# tsc.net
KiCad netlist of a schematic drawn in EAGLE
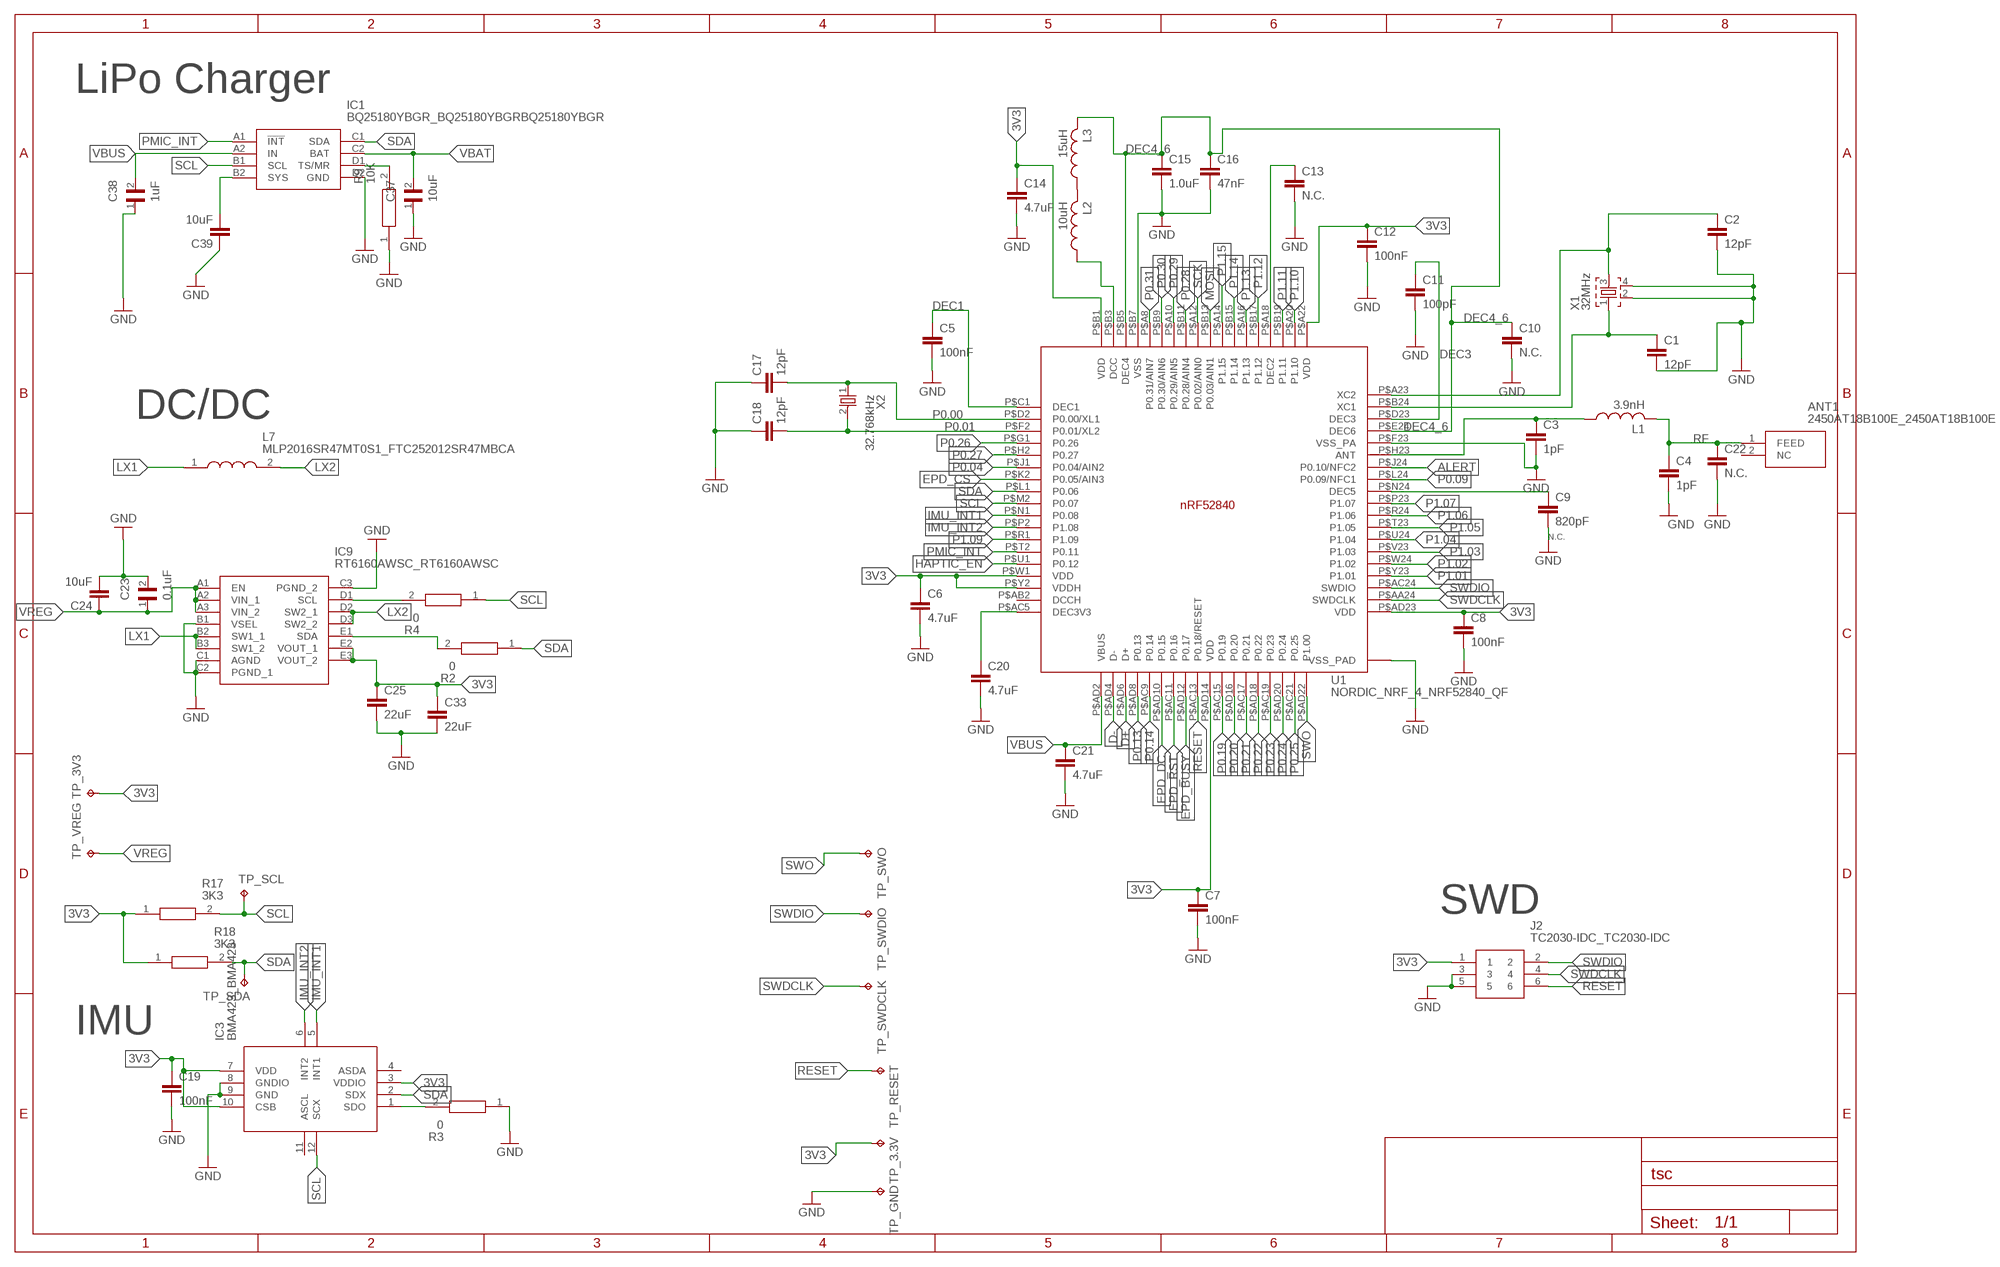
[diagram p0: schematic, sheet 1, part 1 of 2]
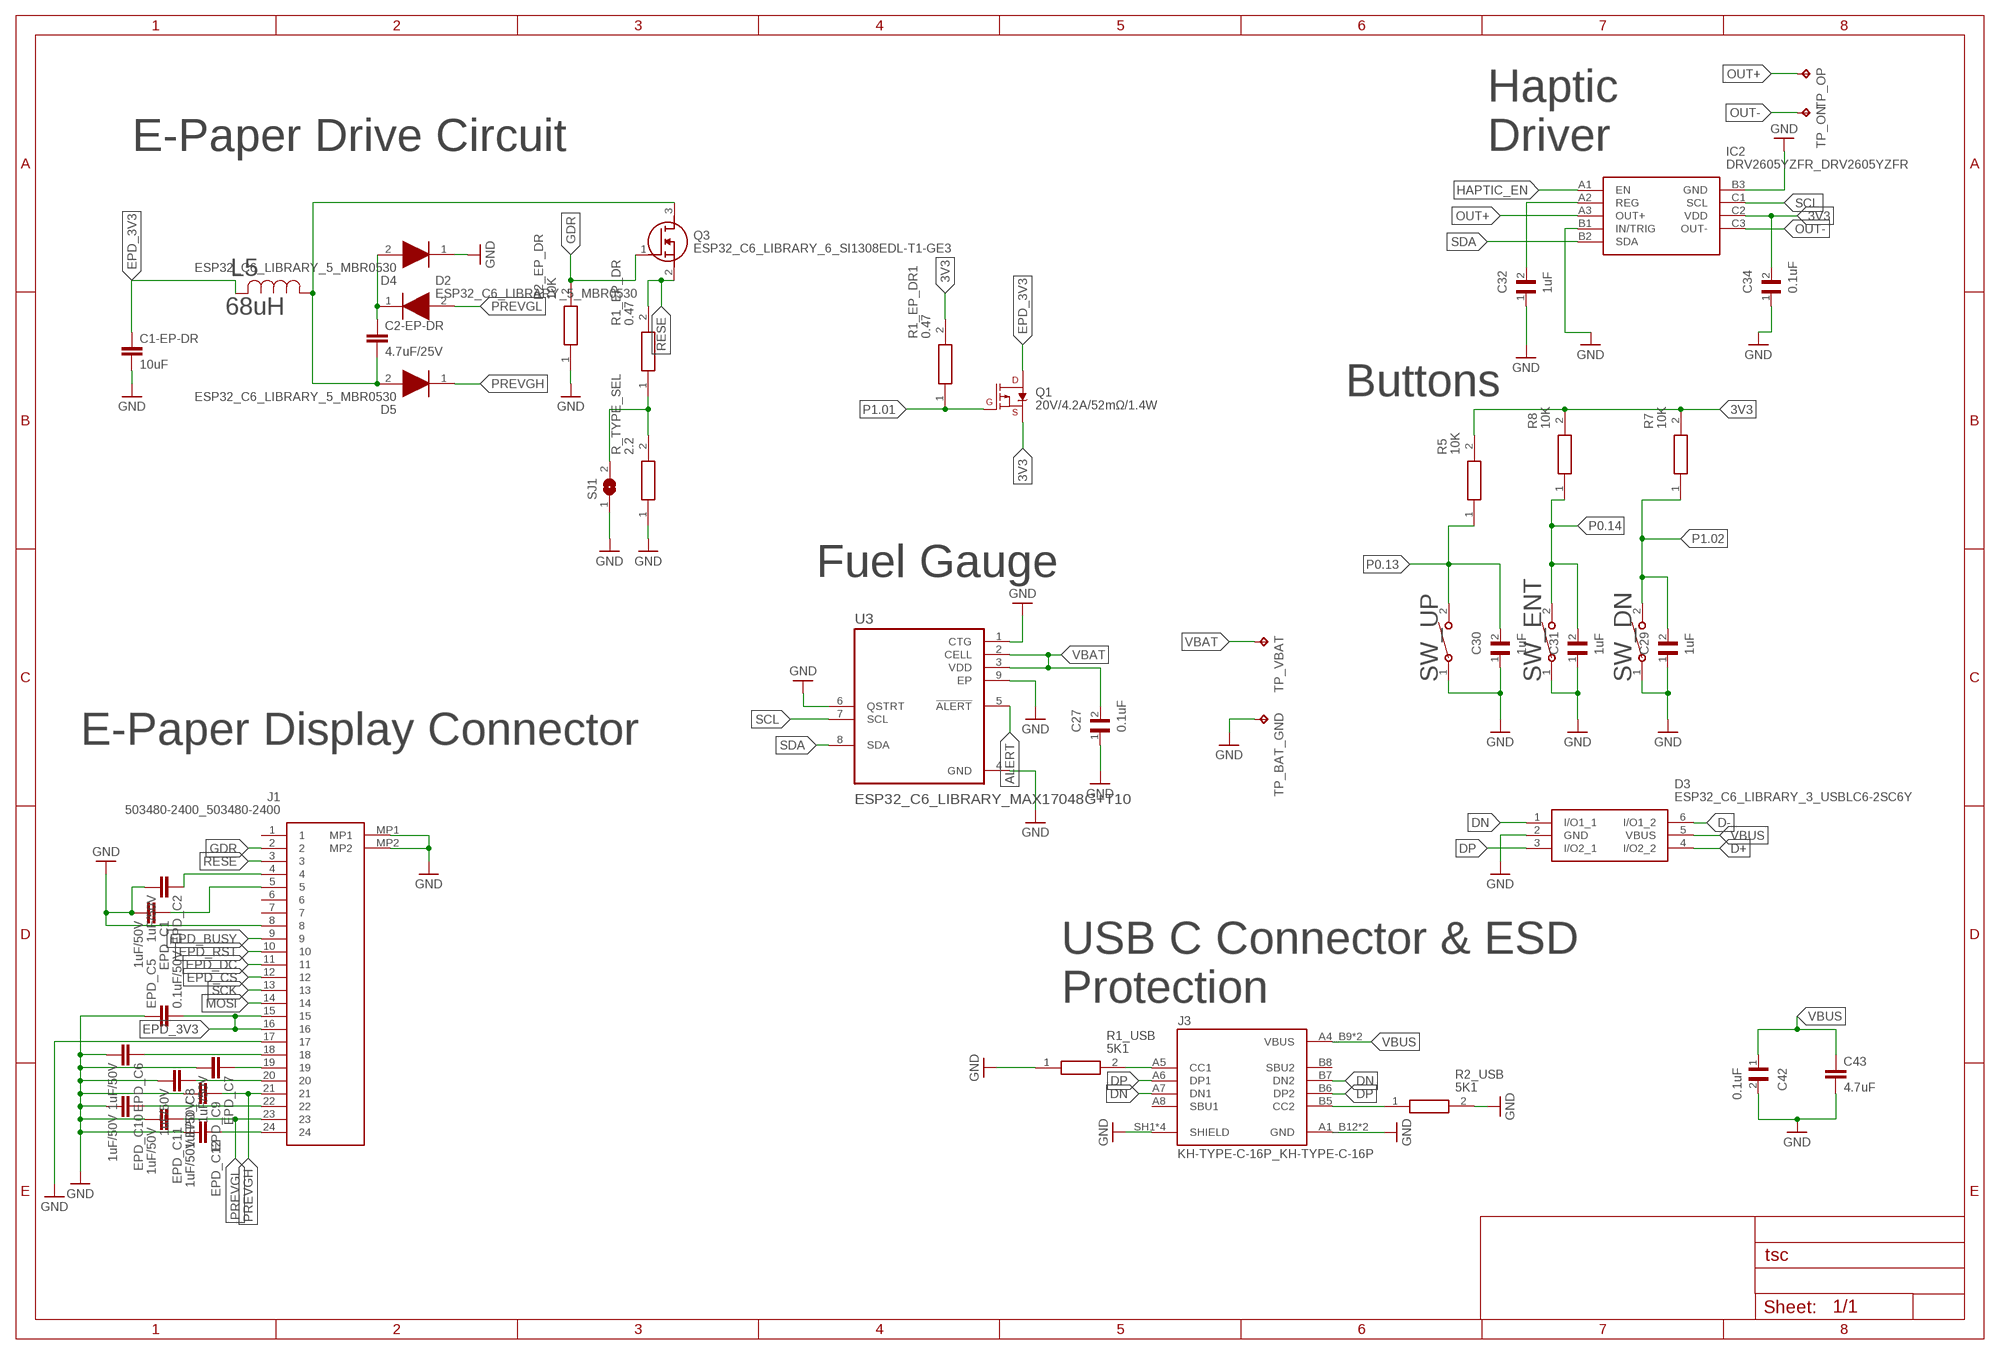
[diagram p1: schematic, sheet 1, part 2 of 2]

(export (version "E")
  (design (tool "Eeschema 10.0.6"))
  (components
    (comp (ref "ANT1")
      (value "2450AT18B100E_2450AT18B100E")
      (footprint "eagle-import:2450AT18B100E_ANTC3216X140N")
      (fields
        (field (name "ARROW_PART_NUMBER") "2450AT18B100E")
        (field (name "MOUSER_PART_NUMBER") "609-2450AT18B100E")
      )
      (libsource (lib "eagle-import") (part "2450AT18B100E_2450AT18B100E"))
    )
    (comp (ref "C1")
      (value "12pF")
      (footprint "eagle-import:NORDIC_NRF_3_RESC0201_L")
      (libsource (lib "eagle-import") (part "NORDIC_NRF_3_CAPACITOR_0201_L"))
    )
    (comp (ref "C1-EP-DR")
      (value "10uF")
      (footprint "eagle-import:NORDIC_NRF_3_RESC0201_L")
      (libsource (lib "eagle-import") (part "NORDIC_NRF_3_CAPACITOR_0201_L"))
    )
    (comp (ref "C2")
      (value "12pF")
      (footprint "eagle-import:NORDIC_NRF_3_RESC0201_L")
      (libsource (lib "eagle-import") (part "NORDIC_NRF_3_CAPACITOR_0201_L"))
    )
    (comp (ref "C2-EP-DR")
      (value "4.7uF/25V")
      (footprint "eagle-import:NORDIC_NRF_3_RESC0201_L")
      (libsource (lib "eagle-import") (part "NORDIC_NRF_3_CAPACITOR_0201_L"))
    )
    (comp (ref "C3")
      (value "1pF")
      (footprint "eagle-import:NORDIC_NRF_3_RESC0201_L")
      (libsource (lib "eagle-import") (part "NORDIC_NRF_3_CAPACITOR_0201_L"))
    )
    (comp (ref "C4")
      (value "1pF")
      (footprint "eagle-import:NORDIC_NRF_3_RESC0201_L")
      (libsource (lib "eagle-import") (part "NORDIC_NRF_3_CAPACITOR_0201_L"))
    )
    (comp (ref "C5")
      (value "100nF")
      (footprint "eagle-import:NORDIC_NRF_3_RESC0201_L")
      (libsource (lib "eagle-import") (part "NORDIC_NRF_3_CAPACITOR_0201_L"))
    )
    (comp (ref "C6")
      (value "4.7uF")
      (footprint "eagle-import:PERFECT_0402_0402")
      (libsource (lib "eagle-import") (part "PERFECT_0402_CAP_0402"))
    )
    (comp (ref "C7")
      (value "100nF")
      (footprint "eagle-import:NORDIC_NRF_3_RESC0201_L")
      (libsource (lib "eagle-import") (part "NORDIC_NRF_3_CAPACITOR_0201_L"))
    )
    (comp (ref "C8")
      (value "100nF")
      (footprint "eagle-import:NORDIC_NRF_3_RESC0201_L")
      (libsource (lib "eagle-import") (part "NORDIC_NRF_3_CAPACITOR_0201_L"))
    )
    (comp (ref "C9")
      (value "820pF")
      (footprint "eagle-import:NORDIC_NRF_3_RESC0201_L")
      (libsource (lib "eagle-import") (part "NORDIC_NRF_3_CAPACITOR_0201_L"))
    )
    (comp (ref "C10")
      (value "N.C.")
      (footprint "eagle-import:NORDIC_NRF_3_RESC0201_L")
      (libsource (lib "eagle-import") (part "NORDIC_NRF_3_CAPACITOR_0201_L"))
    )
    (comp (ref "C11")
      (value "100pF")
      (footprint "eagle-import:NORDIC_NRF_3_RESC0201_L")
      (libsource (lib "eagle-import") (part "NORDIC_NRF_3_CAPACITOR_0201_L"))
    )
    (comp (ref "C12")
      (value "100nF")
      (footprint "eagle-import:NORDIC_NRF_3_RESC0201_L")
      (libsource (lib "eagle-import") (part "NORDIC_NRF_3_CAPACITOR_0201_L"))
    )
    (comp (ref "C13")
      (value "N.C.")
      (footprint "eagle-import:NORDIC_NRF_3_RESC0201_L")
      (libsource (lib "eagle-import") (part "NORDIC_NRF_3_CAPACITOR_0201_L"))
    )
    (comp (ref "C14")
      (value "4.7uF")
      (footprint "eagle-import:PERFECT_0402_0402")
      (libsource (lib "eagle-import") (part "PERFECT_0402_CAP_0402"))
    )
    (comp (ref "C15")
      (value "1.0uF")
      (footprint "eagle-import:PERFECT_0402_0402")
      (libsource (lib "eagle-import") (part "PERFECT_0402_CAP_0402"))
    )
    (comp (ref "C16")
      (value "47nF")
      (footprint "eagle-import:NORDIC_NRF_3_RESC0201_L")
      (libsource (lib "eagle-import") (part "NORDIC_NRF_3_CAPACITOR_0201_L"))
    )
    (comp (ref "C17")
      (value "12pF")
      (footprint "eagle-import:NORDIC_NRF_3_RESC0201_L")
      (libsource (lib "eagle-import") (part "NORDIC_NRF_3_CAPACITOR_0201_L"))
    )
    (comp (ref "C18")
      (value "12pF")
      (footprint "eagle-import:NORDIC_NRF_3_RESC0201_L")
      (libsource (lib "eagle-import") (part "NORDIC_NRF_3_CAPACITOR_0201_L"))
    )
    (comp (ref "C19")
      (value "100nF")
      (footprint "eagle-import:NORDIC_NRF_3_RESC0201_L")
      (libsource (lib "eagle-import") (part "NORDIC_NRF_3_CAPACITOR_0201_L"))
    )
    (comp (ref "C20")
      (value "4.7uF")
      (footprint "eagle-import:PERFECT_0402_0402")
      (libsource (lib "eagle-import") (part "PERFECT_0402_CAP_0402"))
    )
    (comp (ref "C21")
      (value "4.7uF")
      (footprint "eagle-import:PERFECT_0402_0402")
      (libsource (lib "eagle-import") (part "PERFECT_0402_CAP_0402"))
    )
    (comp (ref "C22")
      (value "N.C.")
      (footprint "eagle-import:NORDIC_NRF_3_RESC0201_L")
      (libsource (lib "eagle-import") (part "NORDIC_NRF_3_CAPACITOR_0201_L"))
    )
    (comp (ref "C23")
      (value "0.1uF")
      (footprint "eagle-import:GRM011R60J152KE01L_1_0201")
      (libsource (lib "eagle-import") (part "GRM011R60J152KE01L_1_GRM011R60J152KE01L"))
    )
    (comp (ref "C24")
      (value "10uF")
      (footprint "eagle-import:NORDIC_NRF_3_RESC0201_L")
      (libsource (lib "eagle-import") (part "NORDIC_NRF_3_CAPACITOR_0201_L"))
    )
    (comp (ref "C25")
      (value "22uF")
      (footprint "eagle-import:NORDIC_NRF_3_RESC0201_L")
      (libsource (lib "eagle-import") (part "NORDIC_NRF_3_CAPACITOR_0201_L"))
    )
    (comp (ref "C27")
      (value "0.1uF")
      (footprint "eagle-import:GRM011R60J152KE01L_1_0201")
      (libsource (lib "eagle-import") (part "GRM011R60J152KE01L_1_GRM011R60J152KE01L"))
    )
    (comp (ref "C29")
      (value "1uF")
      (footprint "eagle-import:GRM011R60J152KE01L_1_0201")
      (libsource (lib "eagle-import") (part "GRM011R60J152KE01L_1_GRM011R60J152KE01L"))
    )
    (comp (ref "C30")
      (value "1uF")
      (footprint "eagle-import:GRM011R60J152KE01L_1_0201")
      (libsource (lib "eagle-import") (part "GRM011R60J152KE01L_1_GRM011R60J152KE01L"))
    )
    (comp (ref "C31")
      (value "1uF")
      (footprint "eagle-import:GRM011R60J152KE01L_1_0201")
      (libsource (lib "eagle-import") (part "GRM011R60J152KE01L_1_GRM011R60J152KE01L"))
    )
    (comp (ref "C32")
      (value "1uF")
      (footprint "eagle-import:GRM011R60J152KE01L_1_0201")
      (libsource (lib "eagle-import") (part "GRM011R60J152KE01L_1_GRM011R60J152KE01L"))
    )
    (comp (ref "C33")
      (value "22uF")
      (footprint "eagle-import:NORDIC_NRF_3_RESC0201_L")
      (libsource (lib "eagle-import") (part "NORDIC_NRF_3_CAPACITOR_0201_L"))
    )
    (comp (ref "C34")
      (value "0.1uF")
      (footprint "eagle-import:GRM011R60J152KE01L_1_0201")
      (libsource (lib "eagle-import") (part "GRM011R60J152KE01L_1_GRM011R60J152KE01L"))
    )
    (comp (ref "C37")
      (value "10uF")
      (footprint "eagle-import:GRM011R60J152KE01L_1_0201")
      (libsource (lib "eagle-import") (part "GRM011R60J152KE01L_1_GRM011R60J152KE01L"))
    )
    (comp (ref "C38")
      (value "1uF")
      (footprint "eagle-import:GRM011R60J152KE01L_1_0201")
      (libsource (lib "eagle-import") (part "GRM011R60J152KE01L_1_GRM011R60J152KE01L"))
    )
    (comp (ref "C39")
      (value "10uF")
      (footprint "eagle-import:NORDIC_NRF_3_RESC0201_L")
      (libsource (lib "eagle-import") (part "NORDIC_NRF_3_CAPACITOR_0201_L"))
    )
    (comp (ref "C42")
      (value "0.1uF")
      (footprint "eagle-import:GRM011R60J152KE01L_1_0201")
      (libsource (lib "eagle-import") (part "GRM011R60J152KE01L_1_GRM011R60J152KE01L"))
    )
    (comp (ref "C43")
      (value "4.7uF")
      (footprint "eagle-import:NORDIC_NRF_3_RESC0201_L")
      (libsource (lib "eagle-import") (part "NORDIC_NRF_3_CAPACITOR_0201_L"))
    )
    (comp (ref "D2")
      (value "ESP32_C6_LIBRARY_5_MBR0530")
      (footprint "eagle-import:ESP32_C6_LIBRARY_5_SOD3716X135N")
      (fields (field (name "MF") "ON Semiconductor") (field (name "MP") "MBR0530"))
      (libsource (lib "eagle-import") (part "ESP32_C6_LIBRARY_5_MBR0530"))
    )
    (comp (ref "D3")
      (value "ESP32_C6_LIBRARY_3_USBLC6-2SC6Y")
      (footprint "eagle-import:ESP32_C6_LIBRARY_3_SOT95P280X145-6N")
      (fields (field (name "MF") "STMicroelectronics") (field (name "MP") "USBLC6-2SC6Y"))
      (libsource (lib "eagle-import") (part "ESP32_C6_LIBRARY_3_USBLC6-2SC6Y"))
    )
    (comp (ref "D4")
      (value "ESP32_C6_LIBRARY_5_MBR0530")
      (footprint "eagle-import:ESP32_C6_LIBRARY_5_SOD3716X135N")
      (fields (field (name "MF") "ON Semiconductor") (field (name "MP") "MBR0530"))
      (libsource (lib "eagle-import") (part "ESP32_C6_LIBRARY_5_MBR0530"))
    )
    (comp (ref "D5")
      (value "ESP32_C6_LIBRARY_5_MBR0530")
      (footprint "eagle-import:ESP32_C6_LIBRARY_5_SOD3716X135N")
      (fields (field (name "MF") "ON Semiconductor") (field (name "MP") "MBR0530"))
      (libsource (lib "eagle-import") (part "ESP32_C6_LIBRARY_5_MBR0530"))
    )
    (comp (ref "EPD_C1")
      (value "1uF/50V")
      (footprint "eagle-import:NORDIC_NRF_3_RESC0201_L")
      (libsource (lib "eagle-import") (part "NORDIC_NRF_3_CAPACITOR_0201_L"))
    )
    (comp (ref "EPD_C2")
      (value "1uF/50V")
      (footprint "eagle-import:NORDIC_NRF_3_RESC0201_L")
      (libsource (lib "eagle-import") (part "NORDIC_NRF_3_CAPACITOR_0201_L"))
    )
    (comp (ref "EPD_C5")
      (value "0.1uF/50V")
      (footprint "eagle-import:NORDIC_NRF_3_RESC0201_L")
      (libsource (lib "eagle-import") (part "NORDIC_NRF_3_CAPACITOR_0201_L"))
    )
    (comp (ref "EPD_C6")
      (value "1uF/50V")
      (footprint "eagle-import:NORDIC_NRF_3_RESC0201_L")
      (libsource (lib "eagle-import") (part "NORDIC_NRF_3_CAPACITOR_0201_L"))
    )
    (comp (ref "EPD_C7")
      (value "1uF/50V")
      (footprint "eagle-import:NORDIC_NRF_3_RESC0201_L")
      (libsource (lib "eagle-import") (part "NORDIC_NRF_3_CAPACITOR_0201_L"))
    )
    (comp (ref "EPD_C8")
      (value "1uF/50V")
      (footprint "eagle-import:NORDIC_NRF_3_RESC0201_L")
      (libsource (lib "eagle-import") (part "NORDIC_NRF_3_CAPACITOR_0201_L"))
    )
    (comp (ref "EPD_C9")
      (value "1uF/50V")
      (footprint "eagle-import:NORDIC_NRF_3_RESC0201_L")
      (libsource (lib "eagle-import") (part "NORDIC_NRF_3_CAPACITOR_0201_L"))
    )
    (comp (ref "EPD_C10")
      (value "1uF/50V")
      (footprint "eagle-import:NORDIC_NRF_3_RESC0201_L")
      (libsource (lib "eagle-import") (part "NORDIC_NRF_3_CAPACITOR_0201_L"))
    )
    (comp (ref "EPD_C11")
      (value "1uF/50V")
      (footprint "eagle-import:NORDIC_NRF_3_RESC0201_L")
      (libsource (lib "eagle-import") (part "NORDIC_NRF_3_CAPACITOR_0201_L"))
    )
    (comp (ref "EPD_C12")
      (value "1uF/50V")
      (footprint "eagle-import:NORDIC_NRF_3_RESC0201_L")
      (libsource (lib "eagle-import") (part "NORDIC_NRF_3_CAPACITOR_0201_L"))
    )
    (comp (ref "IC1")
      (value "BQ25180YBGR_BQ25180YBGRBQ25180YBGR")
      (footprint "eagle-import:BQ25180YBGR_BGA8C40P2X4_100X155X50")
      (libsource (lib "eagle-import") (part "BQ25180YBGR_BQ25180YBGRBQ25180YBGR"))
    )
    (comp (ref "IC2")
      (value "DRV2605YZFR_DRV2605YZFR")
      (footprint "eagle-import:DRV2605YZFR_BGA9C50P3X3_144X144X62")
      (fields (field (name "ARROW_PART_NUMBER") "DRV2605YZFR"))
      (libsource (lib "eagle-import") (part "DRV2605YZFR_DRV2605YZFR"))
    )
    (comp (ref "IC3")
      (value "BMA423_BMA423")
      (footprint "eagle-import:BMA423_BMA423")
      (fields (field (name "ARROW_PART_NUMBER") "BMA423") (field (name "MOUSER_PART_NUMBER") "262-BMA423"))
      (libsource (lib "eagle-import") (part "BMA423_BMA423"))
    )
    (comp (ref "IC9")
      (value "RT6160AWSC_RT6160AWSC")
      (footprint "eagle-import:RT6160AWSC_BGA15C40P3X5_140X230X60")
      (fields
        (field (name "MANUFACTURER_PART_NUMBER") "RT6160AWSC")
        (field (name "MOUSER_PART_NUMBER") "835-RT6160AWSC")
      )
      (libsource (lib "eagle-import") (part "RT6160AWSC_RT6160AWSC"))
    )
    (comp (ref "J1")
      (value "503480-2400_503480-2400")
      (footprint "eagle-import:503480-2400_5034802400")
      (fields
        (field (name "MANUFACTURER_PART_NUMBER") "503480-2400")
        (field (name "MOUSER_PART_NUMBER") "538-503480-2400")
      )
      (libsource (lib "eagle-import") (part "503480-2400_503480-2400"))
    )
    (comp (ref "J2")
      (value "TC2030-IDC_TC2030-IDC")
      (footprint "eagle-import:TC2030-IDC_TC2030IDC")
      (fields (field (name "MANUFACTURER_PART_NUMBER") "TC2030-IDC"))
      (libsource (lib "eagle-import") (part "TC2030-IDC_TC2030-IDC"))
    )
    (comp (ref "J3")
      (value "KH-TYPE-C-16P_KH-TYPE-C-16P")
      (footprint "eagle-import:KH-TYPE-C-16P_KINGHELM_KH-TYPE-C-16P")
      (fields (field (name "MF") "kinghelm") (field (name "MP") "KH-TYPE-C-16P"))
      (libsource (lib "eagle-import") (part "KH-TYPE-C-16P_KH-TYPE-C-16P"))
    )
    (comp (ref "L1")
      (value "3.9nH")
      (footprint "eagle-import:NORDIC_NRF_2_RESC0402_L")
      (libsource (lib "eagle-import") (part "NORDIC_NRF_2_INDUCTOR_0402_L"))
    )
    (comp (ref "L2")
      (value "10uH")
      (footprint "eagle-import:NORDIC_NRF_2_RESC0402_L")
      (libsource (lib "eagle-import") (part "NORDIC_NRF_2_INDUCTOR_0402_L"))
    )
    (comp (ref "L3")
      (value "15uH")
      (footprint "eagle-import:NORDIC_NRF_2_RESC0402_L")
      (libsource (lib "eagle-import") (part "NORDIC_NRF_2_INDUCTOR_0402_L"))
    )
    (comp (ref "L5")
      (value "68uH")
      (footprint "eagle-import:ESP32_C6_LIBRARY_2_IND_4828-WE-TPC_WRE")
      (fields
        (field (name "MANUFACTURER_PART_NUMBER") "744043680")
        (field (name "COPYRIGHT") "Copyright (C) 2024 Ultra Librarian. All rights reserved.")
      )
      (libsource (lib "eagle-import") (part "ESP32_C6_LIBRARY_2_744043680IND_4828-WE-TPC_WRE"))
    )
    (comp (ref "L7")
      (value "MLP2016SR47MT0S1_FTC252012SR47MBCA")
      (footprint "eagle-import:MLP2016SR47MT0S1_INDC2016X100N")
      (fields (field (name "MANUFACTURER_PART_NUMBER") "FTC252012SR47MBCA"))
      (libsource (lib "eagle-import") (part "MLP2016SR47MT0S1_FTC252012SR47MBCA"))
    )
    (comp (ref "Q1")
      (value "20V/4.2A/52mΩ/1.4W")
      (footprint "eagle-import:ESP32_C6_LIBRARY_4_ESP32_C6_LIBRARY_4_ESP32_C6_LIBRARY_4_ESP32_C6_LIBRARY_4_ESP32_WROVER_SPARKFUN-DISCRETESEMI_SOT23-3")
      (libsource (lib "eagle-import") (part "ESP32_C6_LIBRARY_4_ESP32_WROVER_SPARKFUN-DISCRETESEMI_MOSFET_PCH-DMG2305UX-7"))
    )
    (comp (ref "Q3")
      (value "ESP32_C6_LIBRARY_6_SI1308EDL-T1-GE3")
      (footprint "eagle-import:ESP32_C6_LIBRARY_6_SOT65P210X110-3N")
      (fields (field (name "MF") "Vishay Siliconix") (field (name "MP") "SI1308EDL-T1-GE3"))
      (libsource (lib "eagle-import") (part "ESP32_C6_LIBRARY_6_SI1308EDL-T1-GE3"))
    )
    (comp (ref "R1_EP_DR")
      (value "0.47")
      (footprint "eagle-import:CPF0201D7K68C1_0201")
      (libsource (lib "eagle-import") (part "CPF0201D7K68C1_CPF0201D7K68C1"))
    )
    (comp (ref "R1_EP_DR1")
      (value "0.47")
      (footprint "eagle-import:CPF0201D7K68C1_0201")
      (libsource (lib "eagle-import") (part "CPF0201D7K68C1_CPF0201D7K68C1"))
    )
    (comp (ref "R1_USB")
      (value "5K1")
      (footprint "eagle-import:CPF0201D7K68C1_0201")
      (libsource (lib "eagle-import") (part "CPF0201D7K68C1_CPF0201D7K68C1"))
    )
    (comp (ref "R2")
      (value "0")
      (footprint "eagle-import:CPF0201D7K68C1_0201")
      (libsource (lib "eagle-import") (part "CPF0201D7K68C1_CPF0201D7K68C1"))
    )
    (comp (ref "R2_EP_DR")
      (value "10K")
      (footprint "eagle-import:CPF0201D7K68C1_0201")
      (libsource (lib "eagle-import") (part "CPF0201D7K68C1_CPF0201D7K68C1"))
    )
    (comp (ref "R2_USB")
      (value "5K1")
      (footprint "eagle-import:CPF0201D7K68C1_0201")
      (libsource (lib "eagle-import") (part "CPF0201D7K68C1_CPF0201D7K68C1"))
    )
    (comp (ref "R3")
      (value "0")
      (footprint "eagle-import:CPF0201D7K68C1_0201")
      (libsource (lib "eagle-import") (part "CPF0201D7K68C1_CPF0201D7K68C1"))
    )
    (comp (ref "R4")
      (value "0")
      (footprint "eagle-import:CPF0201D7K68C1_0201")
      (libsource (lib "eagle-import") (part "CPF0201D7K68C1_CPF0201D7K68C1"))
    )
    (comp (ref "R5")
      (value "10K")
      (footprint "eagle-import:CPF0201D7K68C1_0201")
      (libsource (lib "eagle-import") (part "CPF0201D7K68C1_CPF0201D7K68C1"))
    )
    (comp (ref "R7")
      (value "10K")
      (footprint "eagle-import:CPF0201D7K68C1_0201")
      (libsource (lib "eagle-import") (part "CPF0201D7K68C1_CPF0201D7K68C1"))
    )
    (comp (ref "R8")
      (value "10K")
      (footprint "eagle-import:CPF0201D7K68C1_0201")
      (libsource (lib "eagle-import") (part "CPF0201D7K68C1_CPF0201D7K68C1"))
    )
    (comp (ref "R9")
      (value "10K")
      (footprint "eagle-import:CPF0201D7K68C1_0201")
      (libsource (lib "eagle-import") (part "CPF0201D7K68C1_CPF0201D7K68C1"))
    )
    (comp (ref "R17")
      (value "3K3")
      (footprint "eagle-import:CPF0201D7K68C1_0201")
      (libsource (lib "eagle-import") (part "CPF0201D7K68C1_CPF0201D7K68C1"))
    )
    (comp (ref "R18")
      (value "3K3")
      (footprint "eagle-import:CPF0201D7K68C1_0201")
      (libsource (lib "eagle-import") (part "CPF0201D7K68C1_CPF0201D7K68C1"))
    )
    (comp (ref "R_TYPE_SEL")
      (value "2.2")
      (footprint "eagle-import:CPF0201D7K68C1_0201")
      (libsource (lib "eagle-import") (part "CPF0201D7K68C1_CPF0201D7K68C1"))
    )
    (comp (ref "SJ1")
      (value "ESP32_C6_LIBRARY_7_JUMPER_SJ")
      (footprint "eagle-import:ESP32_C6_LIBRARY_7_JUMPER_SJ")
      (libsource (lib "eagle-import") (part "ESP32_C6_LIBRARY_7_JUMPER_SJ"))
    )
    (comp (ref "SW_DN")
      (value "2025-10-22_07-23-44_LIBRARY_EVP-AKE31ASW_EVP-AKE31A_PAN")
      (footprint "eagle-import:2025-10-22_07-23-44_LIBRARY_SW_EVP-AKE31A_PAN")
      (fields
        (field (name "MANUFACTURER_PART_NUMBER") "EVP-AKE31A")
        (field (name "COPYRIGHT") "Copyright (C) 2025 Ultra Librarian. All rights reserved.")
      )
      (libsource (lib "eagle-import") (part "2025-10-22_07-23-44_LIBRARY_EVP-AKE31ASW_EVP-AKE31A_PAN"))
    )
    (comp (ref "SW_ENT")
      (value "2025-10-22_07-23-44_LIBRARY_EVP-AKE31ASW_EVP-AKE31A_PAN")
      (footprint "eagle-import:2025-10-22_07-23-44_LIBRARY_SW_EVP-AKE31A_PAN")
      (fields
        (field (name "MANUFACTURER_PART_NUMBER") "EVP-AKE31A")
        (field (name "COPYRIGHT") "Copyright (C) 2025 Ultra Librarian. All rights reserved.")
      )
      (libsource (lib "eagle-import") (part "2025-10-22_07-23-44_LIBRARY_EVP-AKE31ASW_EVP-AKE31A_PAN"))
    )
    (comp (ref "SW_UP")
      (value "2025-10-22_07-23-44_LIBRARY_EVP-AKE31ASW_EVP-AKE31A_PAN")
      (footprint "eagle-import:2025-10-22_07-23-44_LIBRARY_SW_EVP-AKE31A_PAN")
      (fields
        (field (name "MANUFACTURER_PART_NUMBER") "EVP-AKE31A")
        (field (name "COPYRIGHT") "Copyright (C) 2025 Ultra Librarian. All rights reserved.")
      )
      (libsource (lib "eagle-import") (part "2025-10-22_07-23-44_LIBRARY_EVP-AKE31ASW_EVP-AKE31A_PAN"))
    )
    (comp (ref "TP_3.3V")
      (value "HECTOR_WATCH_1_TPTP20R")
      (footprint "eagle-import:HECTOR_WATCH_1_TP20R")
      (libsource (lib "eagle-import") (part "HECTOR_WATCH_1_TPTP20R"))
    )
    (comp (ref "TP_3V3")
      (value "HECTOR_WATCH_1_TPTP20R")
      (footprint "eagle-import:HECTOR_WATCH_1_TP20R")
      (libsource (lib "eagle-import") (part "HECTOR_WATCH_1_TPTP20R"))
    )
    (comp (ref "TP_BAT_GND")
      (value "HECTOR_WATCH_1_TPTP20R")
      (footprint "eagle-import:HECTOR_WATCH_1_TP20R")
      (libsource (lib "eagle-import") (part "HECTOR_WATCH_1_TPTP20R"))
    )
    (comp (ref "TP_GND")
      (value "HECTOR_WATCH_1_TPTP20R")
      (footprint "eagle-import:HECTOR_WATCH_1_TP20R")
      (libsource (lib "eagle-import") (part "HECTOR_WATCH_1_TPTP20R"))
    )
    (comp (ref "TP_ON")
      (value "HECTOR_WATCH_1_TPTP20R")
      (footprint "eagle-import:HECTOR_WATCH_1_TP20R")
      (libsource (lib "eagle-import") (part "HECTOR_WATCH_1_TPTP20R"))
    )
    (comp (ref "TP_OP")
      (value "HECTOR_WATCH_1_TPTP20R")
      (footprint "eagle-import:HECTOR_WATCH_1_TP20R")
      (libsource (lib "eagle-import") (part "HECTOR_WATCH_1_TPTP20R"))
    )
    (comp (ref "TP_RESET")
      (value "HECTOR_WATCH_1_TPTP20R")
      (footprint "eagle-import:HECTOR_WATCH_1_TP20R")
      (libsource (lib "eagle-import") (part "HECTOR_WATCH_1_TPTP20R"))
    )
    (comp (ref "TP_SCL")
      (value "HECTOR_WATCH_1_TPTP20R")
      (footprint "eagle-import:HECTOR_WATCH_1_TP20R")
      (libsource (lib "eagle-import") (part "HECTOR_WATCH_1_TPTP20R"))
    )
    (comp (ref "TP_SDA")
      (value "HECTOR_WATCH_1_TPTP20R")
      (footprint "eagle-import:HECTOR_WATCH_1_TP20R")
      (libsource (lib "eagle-import") (part "HECTOR_WATCH_1_TPTP20R"))
    )
    (comp (ref "TP_SWDCLK")
      (value "HECTOR_WATCH_1_TPTP20R")
      (footprint "eagle-import:HECTOR_WATCH_1_TP20R")
      (libsource (lib "eagle-import") (part "HECTOR_WATCH_1_TPTP20R"))
    )
    (comp (ref "TP_SWDIO")
      (value "HECTOR_WATCH_1_TPTP20R")
      (footprint "eagle-import:HECTOR_WATCH_1_TP20R")
      (libsource (lib "eagle-import") (part "HECTOR_WATCH_1_TPTP20R"))
    )
    (comp (ref "TP_SWO")
      (value "HECTOR_WATCH_1_TPTP20R")
      (footprint "eagle-import:HECTOR_WATCH_1_TP20R")
      (libsource (lib "eagle-import") (part "HECTOR_WATCH_1_TPTP20R"))
    )
    (comp (ref "TP_VBAT")
      (value "HECTOR_WATCH_1_TPTP20R")
      (footprint "eagle-import:HECTOR_WATCH_1_TP20R")
      (libsource (lib "eagle-import") (part "HECTOR_WATCH_1_TPTP20R"))
    )
    (comp (ref "TP_VREG")
      (value "HECTOR_WATCH_1_TPTP20R")
      (footprint "eagle-import:HECTOR_WATCH_1_TP20R")
      (libsource (lib "eagle-import") (part "HECTOR_WATCH_1_TPTP20R"))
    )
    (comp (ref "U1")
      (value "NORDIC_NRF_4_NRF52840_QF")
      (footprint "eagle-import:NORDIC_NRF_4_AQFN50P700X700X85_HS-74N")
      (libsource (lib "eagle-import") (part "NORDIC_NRF_4_NRF52840_QF"))
    )
    (comp (ref "U3")
      (value "ESP32_C6_LIBRARY_MAX17048G+T10")
      (footprint "eagle-import:ESP32_C6_LIBRARY_SON50P200X200X80-9N")
      (fields (field (name "MF") "Analog Devices") (field (name "MP") "MAX17048G+T10"))
      (libsource (lib "eagle-import") (part "ESP32_C6_LIBRARY_MAX17048G+T10"))
    )
    (comp (ref "X1")
      (value "32MHz")
      (footprint "eagle-import:NORDIC_NRF_BT-XTAL_2016_N")
      (libsource (lib "eagle-import") (part "NORDIC_NRF_XTAL_32MHZ"))
    )
    (comp (ref "X2")
      (value "32.768kHz")
      (footprint "eagle-import:NORDIC_NRF_1_XTAL_3215_N")
      (libsource (lib "eagle-import") (part "NORDIC_NRF_1_XTAL_32KHZ"))
    )
  )
  (nets
    (net (code "1") (name "/DEC1") (class "Default")
      (node (ref "C5") (pin "1") (pinfunction "1_1") (pintype "passive"))
      (node (ref "U1") (pin "P$C1") (pinfunction "DEC1_P$C1") (pintype "power_in"))
    )
    (net (code "2") (name "/DEC3") (class "Default")
      (node (ref "C11") (pin "1") (pinfunction "1_1") (pintype "passive"))
      (node (ref "C20") (pin "1") (pinfunction "1_1") (pintype "passive"))
      (node (ref "U1") (pin "P$AC5") (pinfunction "DEC3V3_P$AC5") (pintype "bidirectional"))
      (node (ref "U1") (pin "P$D23") (pinfunction "DEC3_P$D23") (pintype "bidirectional"))
    )
    (net (code "3") (name "/DEC4_6") (class "Default")
      (node (ref "C10") (pin "1") (pinfunction "1_1") (pintype "passive"))
      (node (ref "C15") (pin "1") (pinfunction "1_1") (pintype "passive"))
      (node (ref "C16") (pin "1") (pinfunction "1_1") (pintype "passive"))
      (node (ref "L3") (pin "2") (pinfunction "2_2") (pintype "passive"))
      (node (ref "U1") (pin "P$B5") (pinfunction "DEC4_P$B5") (pintype "power_in"))
      (node (ref "U1") (pin "P$E24") (pinfunction "DEC6_P$E24") (pintype "bidirectional"))
    )
    (net (code "4") (name "/P0.00") (class "Default")
      (node (ref "C17") (pin "2") (pinfunction "2_2") (pintype "passive"))
      (node (ref "U1") (pin "P$D2") (pinfunction "P0.00/XL1_P$D2") (pintype "bidirectional"))
      (node (ref "X2") (pin "1") (pinfunction "1_1") (pintype "passive"))
    )
    (net (code "5") (name "/P0.01") (class "Default")
      (node (ref "C18") (pin "2") (pinfunction "2_2") (pintype "passive"))
      (node (ref "U1") (pin "P$F2") (pinfunction "P0.01/XL2_P$F2") (pintype "bidirectional"))
      (node (ref "X2") (pin "2") (pinfunction "2_2") (pintype "passive"))
    )
    (net (code "6") (name "/RF") (class "Default")
      (node (ref "ANT1") (pin "1") (pinfunction "FEED_1") (pintype "input"))
      (node (ref "C22") (pin "1") (pinfunction "1_1") (pintype "passive"))
      (node (ref "C4") (pin "1") (pinfunction "1_1") (pintype "passive"))
      (node (ref "L1") (pin "2") (pinfunction "2_2") (pintype "passive"))
    )
    (net (code "7") (name "3V3") (class "Default")
      (node (ref "C12") (pin "1") (pinfunction "1_1") (pintype "passive"))
      (node (ref "C14") (pin "1") (pinfunction "1_1") (pintype "passive"))
      (node (ref "C19") (pin "1") (pinfunction "1_1") (pintype "passive"))
      (node (ref "C25") (pin "1") (pinfunction "1_1") (pintype "passive"))
      (node (ref "C33") (pin "1") (pinfunction "1_1") (pintype "passive"))
      (node (ref "C34") (pin "2") (pinfunction "2_2") (pintype "passive"))
      (node (ref "C6") (pin "1") (pinfunction "1_1") (pintype "passive"))
      (node (ref "C7") (pin "1") (pinfunction "1_1") (pintype "passive"))
      (node (ref "C8") (pin "1") (pinfunction "1_1") (pintype "passive"))
      (node (ref "IC2") (pin "C2") (pinfunction "VDD_C2") (pintype "bidirectional"))
      (node (ref "IC3") (pin "10") (pinfunction "CSB_10") (pintype "bidirectional"))
      (node (ref "IC3") (pin "3") (pinfunction "VDDIO_3") (pintype "bidirectional"))
      (node (ref "IC3") (pin "7") (pinfunction "VDD_7") (pintype "bidirectional"))
      (node (ref "IC9") (pin "E2") (pinfunction "VOUT_1_E2") (pintype "bidirectional"))
      (node (ref "IC9") (pin "E3") (pinfunction "VOUT_2_E3") (pintype "bidirectional"))
      (node (ref "J2") (pin "1") (pinfunction "1_1") (pintype "bidirectional"))
      (node (ref "Q1") (pin "2") (pinfunction "S_2") (pintype "bidirectional"))
      (node (ref "R17") (pin "1") (pinfunction "1_1") (pintype "bidirectional"))
      (node (ref "R18") (pin "1") (pinfunction "1_1") (pintype "bidirectional"))
      (node (ref "R1_EP_DR1") (pin "2") (pinfunction "2_2") (pintype "bidirectional"))
      (node (ref "R5") (pin "2") (pinfunction "2_2") (pintype "bidirectional"))
      (node (ref "R7") (pin "2") (pinfunction "2_2") (pintype "bidirectional"))
      (node (ref "R8") (pin "2") (pinfunction "2_2") (pintype "bidirectional"))
      (node (ref "TP_3.3V") (pin "TP") (pinfunction "TP_TP") (pintype "input"))
      (node (ref "TP_3V3") (pin "TP") (pinfunction "TP_TP") (pintype "input"))
      (node (ref "U1") (pin "P$A22") (pinfunction "VDD_P$A22") (pintype "power_in"))
      (node (ref "U1") (pin "P$AD14") (pinfunction "VDD_P$AD14") (pintype "power_in"))
      (node (ref "U1") (pin "P$AD23") (pinfunction "VDD_P$AD23") (pintype "power_in"))
      (node (ref "U1") (pin "P$B1") (pinfunction "VDD_P$B1") (pintype "power_in"))
      (node (ref "U1") (pin "P$W1") (pinfunction "VDD_P$W1") (pintype "power_in"))
      (node (ref "U1") (pin "P$Y2") (pinfunction "VDDH_P$Y2") (pintype "power_in"))
    )
    (net (code "8") (name "ALERT") (class "Default")
      (node (ref "U1") (pin "P$J24") (pinfunction "P0.10/NFC2_P$J24") (pintype "bidirectional"))
      (node (ref "U3") (pin "5") (pinfunction "~{ALERT}_5") (pintype "output"))
    )
    (net (code "9") (name "D+") (class "Default")
      (node (ref "D3") (pin "4") (pinfunction "I/O2_2_4") (pintype "bidirectional"))
      (node (ref "U1") (pin "P$AD6") (pinfunction "D+_P$AD6") (pintype "bidirectional"))
    )
    (net (code "10") (name "D-") (class "Default")
      (node (ref "D3") (pin "6") (pinfunction "I/O1_2_6") (pintype "bidirectional"))
      (node (ref "U1") (pin "P$AD4") (pinfunction "D-_P$AD4") (pintype "bidirectional"))
    )
    (net (code "11") (name "DN") (class "Default")
      (node (ref "D3") (pin "1") (pinfunction "I/O1_1_1") (pintype "bidirectional"))
      (node (ref "J3") (pin "A7") (pinfunction "DN1_A7") (pintype "bidirectional"))
      (node (ref "J3") (pin "B7") (pinfunction "DN2_B7") (pintype "bidirectional"))
    )
    (net (code "12") (name "DP") (class "Default")
      (node (ref "D3") (pin "3") (pinfunction "I/O2_1_3") (pintype "bidirectional"))
      (node (ref "J3") (pin "A6") (pinfunction "DP1_A6") (pintype "bidirectional"))
      (node (ref "J3") (pin "B6") (pinfunction "DP2_B6") (pintype "bidirectional"))
    )
    (net (code "13") (name "EPD_3V3") (class "Default")
      (node (ref "C1-EP-DR") (pin "1") (pinfunction "1_1") (pintype "passive"))
      (node (ref "EPD_C5") (pin "2") (pinfunction "2_2") (pintype "passive"))
      (node (ref "J1") (pin "15") (pinfunction "15_15") (pintype "bidirectional"))
      (node (ref "J1") (pin "16") (pinfunction "16_16") (pintype "bidirectional"))
      (node (ref "L5") (pin "2") (pinfunction "2_2") (pintype "passive"))
      (node (ref "Q1") (pin "3") (pinfunction "D_3") (pintype "bidirectional"))
    )
    (net (code "14") (name "EPD_BUSY") (class "Default")
      (node (ref "J1") (pin "9") (pinfunction "9_9") (pintype "bidirectional"))
      (node (ref "U1") (pin "P$AD12") (pinfunction "P0.17_P$AD12") (pintype "bidirectional"))
    )
    (net (code "15") (name "EPD_CS") (class "Default")
      (node (ref "J1") (pin "12") (pinfunction "12_12") (pintype "bidirectional"))
      (node (ref "U1") (pin "P$K2") (pinfunction "P0.05/AIN3_P$K2") (pintype "bidirectional"))
    )
    (net (code "16") (name "EPD_DC") (class "Default")
      (node (ref "J1") (pin "11") (pinfunction "11_11") (pintype "bidirectional"))
      (node (ref "U1") (pin "P$AD10") (pinfunction "P0.15_P$AD10") (pintype "bidirectional"))
    )
    (net (code "17") (name "EPD_RST") (class "Default")
      (node (ref "J1") (pin "10") (pinfunction "10_10") (pintype "bidirectional"))
      (node (ref "U1") (pin "P$AC11") (pinfunction "P0.16_P$AC11") (pintype "bidirectional"))
    )
    (net (code "18") (name "GDR") (class "Default")
      (node (ref "J1") (pin "2") (pinfunction "2_2") (pintype "bidirectional"))
      (node (ref "Q3") (pin "1") (pinfunction "G_1") (pintype "bidirectional"))
      (node (ref "R2_EP_DR") (pin "2") (pinfunction "2_2") (pintype "bidirectional"))
    )
    (net (code "19") (name "GND") (class "Default")
      (node (ref "C1") (pin "2") (pinfunction "2_2") (pintype "passive"))
      (node (ref "C1-EP-DR") (pin "2") (pinfunction "2_2") (pintype "passive"))
      (node (ref "C10") (pin "2") (pinfunction "2_2") (pintype "passive"))
      (node (ref "C11") (pin "2") (pinfunction "2_2") (pintype "passive"))
      (node (ref "C12") (pin "2") (pinfunction "2_2") (pintype "passive"))
      (node (ref "C13") (pin "2") (pinfunction "2_2") (pintype "passive"))
      (node (ref "C14") (pin "2") (pinfunction "2_2") (pintype "passive"))
      (node (ref "C15") (pin "2") (pinfunction "2_2") (pintype "passive"))
      (node (ref "C16") (pin "2") (pinfunction "2_2") (pintype "passive"))
      (node (ref "C17") (pin "1") (pinfunction "1_1") (pintype "passive"))
      (node (ref "C18") (pin "1") (pinfunction "1_1") (pintype "passive"))
      (node (ref "C19") (pin "2") (pinfunction "2_2") (pintype "passive"))
      (node (ref "C2") (pin "2") (pinfunction "2_2") (pintype "passive"))
      (node (ref "C20") (pin "2") (pinfunction "2_2") (pintype "passive"))
      (node (ref "C21") (pin "2") (pinfunction "2_2") (pintype "passive"))
      (node (ref "C22") (pin "2") (pinfunction "2_2") (pintype "passive"))
      (node (ref "C23") (pin "2") (pinfunction "2_2") (pintype "passive"))
      (node (ref "C24") (pin "2") (pinfunction "2_2") (pintype "passive"))
      (node (ref "C25") (pin "2") (pinfunction "2_2") (pintype "passive"))
      (node (ref "C27") (pin "1") (pinfunction "1_1") (pintype "passive"))
      (node (ref "C29") (pin "1") (pinfunction "1_1") (pintype "passive"))
      (node (ref "C3") (pin "2") (pinfunction "2_2") (pintype "passive"))
      (node (ref "C30") (pin "1") (pinfunction "1_1") (pintype "passive"))
      (node (ref "C31") (pin "1") (pinfunction "1_1") (pintype "passive"))
      (node (ref "C32") (pin "1") (pinfunction "1_1") (pintype "passive"))
      (node (ref "C33") (pin "2") (pinfunction "2_2") (pintype "passive"))
      (node (ref "C34") (pin "1") (pinfunction "1_1") (pintype "passive"))
      (node (ref "C37") (pin "1") (pinfunction "1_1") (pintype "passive"))
      (node (ref "C38") (pin "1") (pinfunction "1_1") (pintype "passive"))
      (node (ref "C39") (pin "1") (pinfunction "1_1") (pintype "passive"))
      (node (ref "C4") (pin "2") (pinfunction "2_2") (pintype "passive"))
      (node (ref "C42") (pin "2") (pinfunction "2_2") (pintype "passive"))
      (node (ref "C43") (pin "2") (pinfunction "2_2") (pintype "passive"))
      (node (ref "C5") (pin "2") (pinfunction "2_2") (pintype "passive"))
      (node (ref "C6") (pin "2") (pinfunction "2_2") (pintype "passive"))
      (node (ref "C7") (pin "2") (pinfunction "2_2") (pintype "passive"))
      (node (ref "C8") (pin "2") (pinfunction "2_2") (pintype "passive"))
      (node (ref "C9") (pin "2") (pinfunction "2_2") (pintype "passive"))
      (node (ref "D3") (pin "2") (pinfunction "GND_2") (pintype "bidirectional"))
      (node (ref "D4") (pin "1") (pinfunction "K_1") (pintype "bidirectional"))
      (node (ref "EPD_C1") (pin "2") (pinfunction "2_2") (pintype "passive"))
      (node (ref "EPD_C10") (pin "2") (pinfunction "2_2") (pintype "passive"))
      (node (ref "EPD_C11") (pin "2") (pinfunction "2_2") (pintype "passive"))
      (node (ref "EPD_C12") (pin "2") (pinfunction "2_2") (pintype "passive"))
      (node (ref "EPD_C2") (pin "2") (pinfunction "2_2") (pintype "passive"))
      (node (ref "EPD_C5") (pin "1") (pinfunction "1_1") (pintype "passive"))
      (node (ref "EPD_C6") (pin "2") (pinfunction "2_2") (pintype "passive"))
      (node (ref "EPD_C7") (pin "2") (pinfunction "2_2") (pintype "passive"))
      (node (ref "EPD_C8") (pin "2") (pinfunction "2_2") (pintype "passive"))
      (node (ref "EPD_C9") (pin "2") (pinfunction "2_2") (pintype "passive"))
      (node (ref "IC1") (pin "D2") (pinfunction "GND_D2") (pintype "bidirectional"))
      (node (ref "IC2") (pin "B1") (pinfunction "IN/TRIG_B1") (pintype "bidirectional"))
      (node (ref "IC2") (pin "B3") (pinfunction "GND_B3") (pintype "bidirectional"))
      (node (ref "IC3") (pin "8") (pinfunction "GNDIO_8") (pintype "bidirectional"))
      (node (ref "IC3") (pin "9") (pinfunction "GND_9") (pintype "bidirectional"))
      (node (ref "IC9") (pin "B1") (pinfunction "VSEL_B1") (pintype "bidirectional"))
      (node (ref "IC9") (pin "C1") (pinfunction "AGND_C1") (pintype "bidirectional"))
      (node (ref "IC9") (pin "C2") (pinfunction "PGND_1_C2") (pintype "bidirectional"))
      (node (ref "IC9") (pin "C3") (pinfunction "PGND_2_C3") (pintype "bidirectional"))
      (node (ref "J1") (pin "17") (pinfunction "17_17") (pintype "bidirectional"))
      (node (ref "J1") (pin "8") (pinfunction "8_8") (pintype "bidirectional"))
      (node (ref "J1") (pin "MP1") (pinfunction "MP1_MP1") (pintype "bidirectional"))
      (node (ref "J1") (pin "MP2") (pinfunction "MP2_MP2") (pintype "bidirectional"))
      (node (ref "J2") (pin "3") (pinfunction "3_3") (pintype "bidirectional"))
      (node (ref "J2") (pin "5") (pinfunction "5_5") (pintype "bidirectional"))
      (node (ref "J3") (pin "A12_B1") (pinfunction "GND_A12_B1") (pintype "power_in"))
      (node (ref "J3") (pin "A1_B12") (pinfunction "GND_A1_B12") (pintype "power_in"))
      (node (ref "J3") (pin "SH1") (pinfunction "SHIELD_SH1") (pintype "passive"))
      (node (ref "J3") (pin "SH2") (pinfunction "SHIELD_SH2") (pintype "passive"))
      (node (ref "J3") (pin "SH3") (pinfunction "SHIELD_SH3") (pintype "passive"))
      (node (ref "J3") (pin "SH4") (pinfunction "SHIELD_SH4") (pintype "passive"))
      (node (ref "R1_USB") (pin "1") (pinfunction "1_1") (pintype "bidirectional"))
      (node (ref "R2_EP_DR") (pin "1") (pinfunction "1_1") (pintype "bidirectional"))
      (node (ref "R2_USB") (pin "2") (pinfunction "2_2") (pintype "bidirectional"))
      (node (ref "R3") (pin "1") (pinfunction "1_1") (pintype "bidirectional"))
      (node (ref "R9") (pin "1") (pinfunction "1_1") (pintype "bidirectional"))
      (node (ref "R_TYPE_SEL") (pin "1") (pinfunction "1_1") (pintype "bidirectional"))
      (node (ref "SJ1") (pin "1") (pinfunction "1_1") (pintype "passive"))
      (node (ref "SW_DN") (pin "1") (pinfunction "1_1") (pintype "passive"))
      (node (ref "SW_ENT") (pin "1") (pinfunction "1_1") (pintype "passive"))
      (node (ref "SW_UP") (pin "1") (pinfunction "1_1") (pintype "passive"))
      (node (ref "TP_BAT_GND") (pin "TP") (pinfunction "TP_TP") (pintype "input"))
      (node (ref "TP_GND") (pin "TP") (pinfunction "TP_TP") (pintype "input"))
      (node (ref "U1") (pin "P$74") (pinfunction "VSS_PAD_P$74") (pintype "bidirectional"))
      (node (ref "U1") (pin "P$75") (pinfunction "VSS_PAD_P$75") (pintype "bidirectional"))
      (node (ref "U1") (pin "P$76") (pinfunction "VSS_PAD_P$76") (pintype "bidirectional"))
      (node (ref "U1") (pin "P$77") (pinfunction "VSS_PAD_P$77") (pintype "bidirectional"))
      (node (ref "U1") (pin "P$78") (pinfunction "VSS_PAD_P$78") (pintype "bidirectional"))
      (node (ref "U1") (pin "P$79") (pinfunction "VSS_PAD_P$79") (pintype "bidirectional"))
      (node (ref "U1") (pin "P$80") (pinfunction "VSS_PAD_P$80") (pintype "bidirectional"))
      (node (ref "U1") (pin "P$81") (pinfunction "VSS_PAD_P$81") (pintype "bidirectional"))
      (node (ref "U1") (pin "P$82") (pinfunction "VSS_PAD_P$82") (pintype "bidirectional"))
      (node (ref "U1") (pin "P$83") (pinfunction "VSS_PAD_P$83") (pintype "bidirectional"))
      (node (ref "U1") (pin "P$84") (pinfunction "VSS_PAD_P$84") (pintype "bidirectional"))
      (node (ref "U1") (pin "P$85") (pinfunction "VSS_PAD_P$85") (pintype "bidirectional"))
      (node (ref "U1") (pin "P$86") (pinfunction "VSS_PAD_P$86") (pintype "bidirectional"))
      (node (ref "U1") (pin "P$87") (pinfunction "VSS_PAD_P$87") (pintype "bidirectional"))
      (node (ref "U1") (pin "P$88") (pinfunction "VSS_PAD_P$88") (pintype "bidirectional"))
      (node (ref "U1") (pin "P$89") (pinfunction "VSS_PAD_P$89") (pintype "bidirectional"))
      (node (ref "U1") (pin "P$90") (pinfunction "VSS_PAD_P$90") (pintype "bidirectional"))
      (node (ref "U1") (pin "P$B7") (pinfunction "VSS_P$B7") (pintype "power_in"))
      (node (ref "U1") (pin "P$F23") (pinfunction "VSS_PA_P$F23") (pintype "bidirectional"))
      (node (ref "U3") (pin "1") (pinfunction "CTG_1") (pintype "power_in"))
      (node (ref "U3") (pin "4") (pinfunction "GND_4") (pintype "power_in"))
      (node (ref "U3") (pin "6") (pinfunction "QSTRT_6") (pintype "input"))
      (node (ref "U3") (pin "9") (pinfunction "EP_9") (pintype "power_in"))
      (node (ref "X1") (pin "2") (pinfunction "2_2") (pintype "passive"))
      (node (ref "X1") (pin "4") (pinfunction "4_4") (pintype "passive"))
    )
    (net (code "20") (name "HAPTIC_EN") (class "Default")
      (node (ref "IC2") (pin "A1") (pinfunction "EN_A1") (pintype "bidirectional"))
      (node (ref "U1") (pin "P$U1") (pinfunction "P0.12_P$U1") (pintype "bidirectional"))
    )
    (net (code "21") (name "IMU_INT1") (class "Default")
      (node (ref "IC3") (pin "5") (pinfunction "INT1_5") (pintype "bidirectional"))
      (node (ref "U1") (pin "P$N1") (pinfunction "P0.08_P$N1") (pintype "bidirectional"))
    )
    (net (code "22") (name "IMU_INT2") (class "Default")
      (node (ref "IC3") (pin "6") (pinfunction "INT2_6") (pintype "bidirectional"))
      (node (ref "U1") (pin "P$P2") (pinfunction "P1.08_P$P2") (pintype "bidirectional"))
    )
    (net (code "23") (name "LX1") (class "Default")
      (node (ref "IC9") (pin "B2") (pinfunction "SW1_1_B2") (pintype "bidirectional"))
      (node (ref "IC9") (pin "B3") (pinfunction "SW1_2_B3") (pintype "bidirectional"))
      (node (ref "L7") (pin "1") (pinfunction "1_1") (pintype "bidirectional"))
    )
    (net (code "24") (name "LX2") (class "Default")
      (node (ref "IC9") (pin "D2") (pinfunction "SW2_1_D2") (pintype "bidirectional"))
      (node (ref "IC9") (pin "D3") (pinfunction "SW2_2_D3") (pintype "bidirectional"))
      (node (ref "L7") (pin "2") (pinfunction "2_2") (pintype "bidirectional"))
    )
    (net (code "25") (name "MOSI") (class "Default")
      (node (ref "J1") (pin "14") (pinfunction "14_14") (pintype "bidirectional"))
      (node (ref "U1") (pin "P$B13") (pinfunction "P0.03/AIN1_P$B13") (pintype "bidirectional"))
    )
    (net (code "26") (name "Net-(D2-K)") (class "Default")
      (node (ref "C2-EP-DR") (pin "1") (pinfunction "1_1") (pintype "passive"))
      (node (ref "D2") (pin "1") (pinfunction "K_1") (pintype "bidirectional"))
      (node (ref "D4") (pin "2") (pinfunction "A_2") (pintype "bidirectional"))
    )
    (net (code "27") (name "Net-(D5-A)") (class "Default")
      (node (ref "C2-EP-DR") (pin "2") (pinfunction "2_2") (pintype "passive"))
      (node (ref "D5") (pin "2") (pinfunction "A_2") (pintype "bidirectional"))
      (node (ref "L5") (pin "1") (pinfunction "1_1") (pintype "passive"))
      (node (ref "Q3") (pin "3") (pinfunction "D_3") (pintype "bidirectional"))
    )
    (net (code "28") (name "Net-(EPD_C1-Pad1)") (class "Default")
      (node (ref "EPD_C1") (pin "1") (pinfunction "1_1") (pintype "passive"))
      (node (ref "J1") (pin "5") (pinfunction "5_5") (pintype "bidirectional"))
    )
    (net (code "29") (name "Net-(EPD_C2-Pad1)") (class "Default")
      (node (ref "EPD_C2") (pin "1") (pinfunction "1_1") (pintype "passive"))
      (node (ref "J1") (pin "4") (pinfunction "4_4") (pintype "bidirectional"))
    )
    (net (code "30") (name "Net-(EPD_C6-Pad1)") (class "Default")
      (node (ref "EPD_C6") (pin "1") (pinfunction "1_1") (pintype "passive"))
      (node (ref "J1") (pin "18") (pinfunction "18_18") (pintype "bidirectional"))
    )
    (net (code "31") (name "Net-(EPD_C7-Pad1)") (class "Default")
      (node (ref "EPD_C7") (pin "1") (pinfunction "1_1") (pintype "passive"))
      (node (ref "J1") (pin "19") (pinfunction "19_19") (pintype "bidirectional"))
    )
    (net (code "32") (name "Net-(EPD_C8-Pad1)") (class "Default")
      (node (ref "EPD_C8") (pin "1") (pinfunction "1_1") (pintype "passive"))
      (node (ref "J1") (pin "20") (pinfunction "20_20") (pintype "bidirectional"))
    )
    (net (code "33") (name "Net-(EPD_C10-Pad1)") (class "Default")
      (node (ref "EPD_C10") (pin "1") (pinfunction "1_1") (pintype "passive"))
      (node (ref "J1") (pin "22") (pinfunction "22_22") (pintype "bidirectional"))
    )
    (net (code "34") (name "Net-(EPD_C12-Pad1)") (class "Default")
      (node (ref "EPD_C12") (pin "1") (pinfunction "1_1") (pintype "passive"))
      (node (ref "J1") (pin "24") (pinfunction "24_24") (pintype "bidirectional"))
    )
    (net (code "35") (name "Net-(IC1-SYS)") (class "Default")
      (node (ref "C39") (pin "2") (pinfunction "2_2") (pintype "passive"))
      (node (ref "IC1") (pin "B2") (pinfunction "SYS_B2") (pintype "bidirectional"))
    )
    (net (code "36") (name "Net-(IC1-TS{slash}MR)") (class "Default")
      (node (ref "IC1") (pin "D1") (pinfunction "TS/MR_D1") (pintype "bidirectional"))
      (node (ref "R9") (pin "2") (pinfunction "2_2") (pintype "bidirectional"))
    )
    (net (code "37") (name "Net-(IC2-REG)") (class "Default")
      (node (ref "C32") (pin "2") (pinfunction "2_2") (pintype "passive"))
      (node (ref "IC2") (pin "A2") (pinfunction "REG_A2") (pintype "bidirectional"))
    )
    (net (code "38") (name "Net-(IC3-SDO)") (class "Default")
      (node (ref "IC3") (pin "1") (pinfunction "SDO_1") (pintype "bidirectional"))
      (node (ref "R3") (pin "2") (pinfunction "2_2") (pintype "bidirectional"))
    )
    (net (code "39") (name "Net-(IC9-SCL)") (class "Default")
      (node (ref "IC9") (pin "D1") (pinfunction "SCL_D1") (pintype "bidirectional"))
      (node (ref "R4") (pin "2") (pinfunction "2_2") (pintype "bidirectional"))
    )
    (net (code "40") (name "Net-(IC9-SDA)") (class "Default")
      (node (ref "IC9") (pin "E1") (pinfunction "SDA_E1") (pintype "bidirectional"))
      (node (ref "R2") (pin "2") (pinfunction "2_2") (pintype "bidirectional"))
    )
    (net (code "41") (name "Net-(J3-CC1)") (class "Default")
      (node (ref "J3") (pin "A5") (pinfunction "CC1_A5") (pintype "bidirectional"))
      (node (ref "R1_USB") (pin "2") (pinfunction "2_2") (pintype "bidirectional"))
    )
    (net (code "42") (name "Net-(J3-CC2)") (class "Default")
      (node (ref "J3") (pin "B5") (pinfunction "CC2_B5") (pintype "bidirectional"))
      (node (ref "R2_USB") (pin "1") (pinfunction "1_1") (pintype "bidirectional"))
    )
    (net (code "43") (name "Net-(L2-Pad2)") (class "Default")
      (node (ref "L2") (pin "2") (pinfunction "2_2") (pintype "passive"))
      (node (ref "L3") (pin "1") (pinfunction "1_1") (pintype "passive"))
    )
    (net (code "44") (name "Net-(R1_EP_DR-Pad1)") (class "Default")
      (node (ref "R1_EP_DR") (pin "1") (pinfunction "1_1") (pintype "bidirectional"))
      (node (ref "R_TYPE_SEL") (pin "2") (pinfunction "2_2") (pintype "bidirectional"))
      (node (ref "SJ1") (pin "2") (pinfunction "2_2") (pintype "passive"))
    )
    (net (code "45") (name "Net-(U1-ANT)") (class "Default")
      (node (ref "C3") (pin "1") (pinfunction "1_1") (pintype "passive"))
      (node (ref "L1") (pin "1") (pinfunction "1_1") (pintype "passive"))
      (node (ref "U1") (pin "P$H23") (pinfunction "ANT_P$H23") (pintype "bidirectional"))
    )
    (net (code "46") (name "Net-(U1-DCC)") (class "Default")
      (node (ref "L2") (pin "1") (pinfunction "1_1") (pintype "passive"))
      (node (ref "U1") (pin "P$B3") (pinfunction "DCC_P$B3") (pintype "output"))
    )
    (net (code "47") (name "Net-(U1-DEC2)") (class "Default")
      (node (ref "C13") (pin "1") (pinfunction "1_1") (pintype "passive"))
      (node (ref "U1") (pin "P$A18") (pinfunction "DEC2_P$A18") (pintype "bidirectional"))
    )
    (net (code "48") (name "Net-(U1-DEC5)") (class "Default")
      (node (ref "C9") (pin "1") (pinfunction "1_1") (pintype "passive"))
      (node (ref "U1") (pin "P$N24") (pinfunction "DEC5_P$N24") (pintype "bidirectional"))
    )
    (net (code "49") (name "Net-(U1-XC1)") (class "Default")
      (node (ref "C1") (pin "1") (pinfunction "1_1") (pintype "passive"))
      (node (ref "U1") (pin "P$B24") (pinfunction "XC1_P$B24") (pintype "input"))
      (node (ref "X1") (pin "1") (pinfunction "1_1") (pintype "passive"))
    )
    (net (code "50") (name "Net-(U1-XC2)") (class "Default")
      (node (ref "C2") (pin "1") (pinfunction "1_1") (pintype "passive"))
      (node (ref "U1") (pin "P$A23") (pinfunction "XC2_P$A23") (pintype "output"))
      (node (ref "X1") (pin "3") (pinfunction "3_3") (pintype "passive"))
    )
    (net (code "51") (name "OUT+") (class "Default")
      (node (ref "IC2") (pin "A3") (pinfunction "OUT+_A3") (pintype "bidirectional"))
      (node (ref "TP_OP") (pin "TP") (pinfunction "TP_TP") (pintype "input"))
    )
    (net (code "52") (name "OUT-") (class "Default")
      (node (ref "IC2") (pin "C3") (pinfunction "OUT-_C3") (pintype "bidirectional"))
      (node (ref "TP_ON") (pin "TP") (pinfunction "TP_TP") (pintype "input"))
    )
    (net (code "53") (name "P0.04") (class "Default")
      (node (ref "U1") (pin "P$J1") (pinfunction "P0.04/AIN2_P$J1") (pintype "bidirectional"))
    )
    (net (code "54") (name "P0.09") (class "Default")
      (node (ref "U1") (pin "P$L24") (pinfunction "P0.09/NFC1_P$L24") (pintype "bidirectional"))
    )
    (net (code "55") (name "P0.13") (class "Default")
      (node (ref "C30") (pin "2") (pinfunction "2_2") (pintype "passive"))
      (node (ref "R5") (pin "1") (pinfunction "1_1") (pintype "bidirectional"))
      (node (ref "SW_UP") (pin "2") (pinfunction "2_2") (pintype "passive"))
      (node (ref "U1") (pin "P$AD8") (pinfunction "P0.13_P$AD8") (pintype "bidirectional"))
    )
    (net (code "56") (name "P0.14") (class "Default")
      (node (ref "C31") (pin "2") (pinfunction "2_2") (pintype "passive"))
      (node (ref "R8") (pin "1") (pinfunction "1_1") (pintype "bidirectional"))
      (node (ref "SW_ENT") (pin "2") (pinfunction "2_2") (pintype "passive"))
      (node (ref "U1") (pin "P$AC9") (pinfunction "P0.14_P$AC9") (pintype "bidirectional"))
    )
    (net (code "57") (name "P0.19") (class "Default")
      (node (ref "U1") (pin "P$AC15") (pinfunction "P0.19_P$AC15") (pintype "bidirectional"))
    )
    (net (code "58") (name "P0.20") (class "Default")
      (node (ref "U1") (pin "P$AD16") (pinfunction "P0.20_P$AD16") (pintype "bidirectional"))
    )
    (net (code "59") (name "P0.21") (class "Default")
      (node (ref "U1") (pin "P$AC17") (pinfunction "P0.21_P$AC17") (pintype "bidirectional"))
    )
    (net (code "60") (name "P0.22") (class "Default")
      (node (ref "U1") (pin "P$AD18") (pinfunction "P0.22_P$AD18") (pintype "bidirectional"))
    )
    (net (code "61") (name "P0.23") (class "Default")
      (node (ref "U1") (pin "P$AC19") (pinfunction "P0.23_P$AC19") (pintype "bidirectional"))
    )
    (net (code "62") (name "P0.24") (class "Default")
      (node (ref "U1") (pin "P$AD20") (pinfunction "P0.24_P$AD20") (pintype "bidirectional"))
    )
    (net (code "63") (name "P0.25") (class "Default")
      (node (ref "U1") (pin "P$AC21") (pinfunction "P0.25_P$AC21") (pintype "bidirectional"))
    )
    (net (code "64") (name "P0.26") (class "Default")
      (node (ref "U1") (pin "P$G1") (pinfunction "P0.26_P$G1") (pintype "bidirectional"))
    )
    (net (code "65") (name "P0.27") (class "Default")
      (node (ref "U1") (pin "P$H2") (pinfunction "P0.27_P$H2") (pintype "bidirectional"))
    )
    (net (code "66") (name "P0.28") (class "Default")
      (node (ref "U1") (pin "P$B11") (pinfunction "P0.28/AIN4_P$B11") (pintype "bidirectional"))
    )
    (net (code "67") (name "P0.29") (class "Default")
      (node (ref "U1") (pin "P$A10") (pinfunction "P0.29/AIN5_P$A10") (pintype "bidirectional"))
    )
    (net (code "68") (name "P0.30") (class "Default")
      (node (ref "U1") (pin "P$B9") (pinfunction "P0.30/AIN6_P$B9") (pintype "bidirectional"))
    )
    (net (code "69") (name "P0.31") (class "Default")
      (node (ref "U1") (pin "P$A8") (pinfunction "P0.31/AIN7_P$A8") (pintype "bidirectional"))
    )
    (net (code "70") (name "P1.01") (class "Default")
      (node (ref "Q1") (pin "1") (pinfunction "G_1") (pintype "bidirectional"))
      (node (ref "R1_EP_DR1") (pin "1") (pinfunction "1_1") (pintype "bidirectional"))
      (node (ref "U1") (pin "P$Y23") (pinfunction "P1.01_P$Y23") (pintype "bidirectional"))
    )
    (net (code "71") (name "P1.02") (class "Default")
      (node (ref "C29") (pin "2") (pinfunction "2_2") (pintype "passive"))
      (node (ref "R7") (pin "1") (pinfunction "1_1") (pintype "bidirectional"))
      (node (ref "SW_DN") (pin "2") (pinfunction "2_2") (pintype "passive"))
      (node (ref "U1") (pin "P$W24") (pinfunction "P1.02_P$W24") (pintype "bidirectional"))
    )
    (net (code "72") (name "P1.03") (class "Default")
      (node (ref "U1") (pin "P$V23") (pinfunction "P1.03_P$V23") (pintype "bidirectional"))
    )
    (net (code "73") (name "P1.04") (class "Default")
      (node (ref "U1") (pin "P$U24") (pinfunction "P1.04_P$U24") (pintype "bidirectional"))
    )
    (net (code "74") (name "P1.05") (class "Default")
      (node (ref "U1") (pin "P$T23") (pinfunction "P1.05_P$T23") (pintype "bidirectional"))
    )
    (net (code "75") (name "P1.06") (class "Default")
      (node (ref "U1") (pin "P$R24") (pinfunction "P1.06_P$R24") (pintype "bidirectional"))
    )
    (net (code "76") (name "P1.07") (class "Default")
      (node (ref "U1") (pin "P$P23") (pinfunction "P1.07_P$P23") (pintype "bidirectional"))
    )
    (net (code "77") (name "P1.09") (class "Default")
      (node (ref "U1") (pin "P$R1") (pinfunction "P1.09_P$R1") (pintype "bidirectional"))
    )
    (net (code "78") (name "P1.10") (class "Default")
      (node (ref "U1") (pin "P$A20") (pinfunction "P1.10_P$A20") (pintype "bidirectional"))
    )
    (net (code "79") (name "P1.11") (class "Default")
      (node (ref "U1") (pin "P$B19") (pinfunction "P1.11_P$B19") (pintype "bidirectional"))
    )
    (net (code "80") (name "P1.12") (class "Default")
      (node (ref "U1") (pin "P$B17") (pinfunction "P1.12_P$B17") (pintype "bidirectional"))
    )
    (net (code "81") (name "P1.13") (class "Default")
      (node (ref "U1") (pin "P$A16") (pinfunction "P1.13_P$A16") (pintype "bidirectional"))
    )
    (net (code "82") (name "P1.14") (class "Default")
      (node (ref "U1") (pin "P$B15") (pinfunction "P1.14_P$B15") (pintype "bidirectional"))
    )
    (net (code "83") (name "P1.15") (class "Default")
      (node (ref "U1") (pin "P$A14") (pinfunction "P1.15_P$A14") (pintype "bidirectional"))
    )
    (net (code "84") (name "PMIC_INT") (class "Default")
      (node (ref "IC1") (pin "A1") (pinfunction "~{INT}_A1") (pintype "bidirectional"))
      (node (ref "U1") (pin "P$T2") (pinfunction "P0.11_P$T2") (pintype "bidirectional"))
    )
    (net (code "85") (name "PREVGH") (class "Default")
      (node (ref "D5") (pin "1") (pinfunction "K_1") (pintype "bidirectional"))
      (node (ref "EPD_C9") (pin "1") (pinfunction "1_1") (pintype "passive"))
      (node (ref "J1") (pin "21") (pinfunction "21_21") (pintype "bidirectional"))
    )
    (net (code "86") (name "PREVGL") (class "Default")
      (node (ref "D2") (pin "2") (pinfunction "A_2") (pintype "bidirectional"))
      (node (ref "EPD_C11") (pin "1") (pinfunction "1_1") (pintype "passive"))
      (node (ref "J1") (pin "23") (pinfunction "23_23") (pintype "bidirectional"))
    )
    (net (code "87") (name "RESE") (class "Default")
      (node (ref "J1") (pin "3") (pinfunction "3_3") (pintype "bidirectional"))
      (node (ref "Q3") (pin "2") (pinfunction "S_2") (pintype "bidirectional"))
      (node (ref "R1_EP_DR") (pin "2") (pinfunction "2_2") (pintype "bidirectional"))
    )
    (net (code "88") (name "RESET") (class "Default")
      (node (ref "J2") (pin "6") (pinfunction "6_6") (pintype "bidirectional"))
      (node (ref "TP_RESET") (pin "TP") (pinfunction "TP_TP") (pintype "input"))
      (node (ref "U1") (pin "P$AC13") (pinfunction "P0.18/RESET_P$AC13") (pintype "bidirectional"))
    )
    (net (code "89") (name "SCK") (class "Default")
      (node (ref "J1") (pin "13") (pinfunction "13_13") (pintype "bidirectional"))
      (node (ref "U1") (pin "P$A12") (pinfunction "P0.02/AIN0_P$A12") (pintype "bidirectional"))
    )
    (net (code "90") (name "SCL") (class "Default")
      (node (ref "IC1") (pin "B1") (pinfunction "SCL_B1") (pintype "bidirectional"))
      (node (ref "IC2") (pin "C1") (pinfunction "SCL_C1") (pintype "bidirectional"))
      (node (ref "IC3") (pin "12") (pinfunction "SCX_12") (pintype "bidirectional"))
      (node (ref "R17") (pin "2") (pinfunction "2_2") (pintype "bidirectional"))
      (node (ref "R4") (pin "1") (pinfunction "1_1") (pintype "bidirectional"))
      (node (ref "TP_SCL") (pin "TP") (pinfunction "TP_TP") (pintype "input"))
      (node (ref "U1") (pin "P$M2") (pinfunction "P0.07_P$M2") (pintype "bidirectional"))
      (node (ref "U3") (pin "7") (pinfunction "SCL_7") (pintype "input"))
    )
    (net (code "91") (name "SDA") (class "Default")
      (node (ref "IC1") (pin "C1") (pinfunction "SDA_C1") (pintype "bidirectional"))
      (node (ref "IC2") (pin "B2") (pinfunction "SDA_B2") (pintype "bidirectional"))
      (node (ref "IC3") (pin "2") (pinfunction "SDX_2") (pintype "bidirectional"))
      (node (ref "R18") (pin "2") (pinfunction "2_2") (pintype "bidirectional"))
      (node (ref "R2") (pin "1") (pinfunction "1_1") (pintype "bidirectional"))
      (node (ref "TP_SDA") (pin "TP") (pinfunction "TP_TP") (pintype "input"))
      (node (ref "U1") (pin "P$L1") (pinfunction "P0.06_P$L1") (pintype "bidirectional"))
      (node (ref "U3") (pin "8") (pinfunction "SDA_8") (pintype "bidirectional"))
    )
    (net (code "92") (name "SWDCLK") (class "Default")
      (node (ref "J2") (pin "4") (pinfunction "4_4") (pintype "bidirectional"))
      (node (ref "TP_SWDCLK") (pin "TP") (pinfunction "TP_TP") (pintype "input"))
      (node (ref "U1") (pin "P$AA24") (pinfunction "SWDCLK_P$AA24") (pintype "input"))
    )
    (net (code "93") (name "SWDIO") (class "Default")
      (node (ref "J2") (pin "2") (pinfunction "2_2") (pintype "bidirectional"))
      (node (ref "TP_SWDIO") (pin "TP") (pinfunction "TP_TP") (pintype "input"))
      (node (ref "U1") (pin "P$AC24") (pinfunction "SWDIO_P$AC24") (pintype "bidirectional"))
    )
    (net (code "94") (name "SWO") (class "Default")
      (node (ref "TP_SWO") (pin "TP") (pinfunction "TP_TP") (pintype "input"))
      (node (ref "U1") (pin "P$AD22") (pinfunction "P1.00_P$AD22") (pintype "bidirectional"))
    )
    (net (code "95") (name "VBAT") (class "Default")
      (node (ref "C27") (pin "2") (pinfunction "2_2") (pintype "passive"))
      (node (ref "C37") (pin "2") (pinfunction "2_2") (pintype "passive"))
      (node (ref "IC1") (pin "C2") (pinfunction "BAT_C2") (pintype "bidirectional"))
      (node (ref "TP_VBAT") (pin "TP") (pinfunction "TP_TP") (pintype "input"))
      (node (ref "U3") (pin "2") (pinfunction "CELL_2") (pintype "power_in"))
      (node (ref "U3") (pin "3") (pinfunction "VDD_3") (pintype "power_in"))
    )
    (net (code "96") (name "VBUS") (class "Default")
      (node (ref "C21") (pin "1") (pinfunction "1_1") (pintype "passive"))
      (node (ref "C38") (pin "2") (pinfunction "2_2") (pintype "passive"))
      (node (ref "C42") (pin "1") (pinfunction "1_1") (pintype "passive"))
      (node (ref "C43") (pin "1") (pinfunction "1_1") (pintype "passive"))
      (node (ref "D3") (pin "5") (pinfunction "VBUS_5") (pintype "bidirectional"))
      (node (ref "IC1") (pin "A2") (pinfunction "IN_A2") (pintype "bidirectional"))
      (node (ref "J3") (pin "A4_B9") (pinfunction "VBUS_A4_B9") (pintype "power_in"))
      (node (ref "J3") (pin "A9_B4") (pinfunction "VBUS_A9_B4") (pintype "power_in"))
      (node (ref "U1") (pin "P$AD2") (pinfunction "VBUS_P$AD2") (pintype "power_in"))
    )
    (net (code "97") (name "VREG") (class "Default")
      (node (ref "C23") (pin "1") (pinfunction "1_1") (pintype "passive"))
      (node (ref "C24") (pin "1") (pinfunction "1_1") (pintype "passive"))
      (node (ref "IC9") (pin "A1") (pinfunction "EN_A1") (pintype "bidirectional"))
      (node (ref "IC9") (pin "A2") (pinfunction "VIN_1_A2") (pintype "bidirectional"))
      (node (ref "IC9") (pin "A3") (pinfunction "VIN_2_A3") (pintype "bidirectional"))
      (node (ref "TP_VREG") (pin "TP") (pinfunction "TP_TP") (pintype "input"))
    )
    (net (code "98") (name "unconnected-(ANT1-NC-Pad2)") (class "Default")
      (node (ref "ANT1") (pin "2") (pinfunction "NC_2") (pintype "no_connect"))
    )
    (net (code "99") (name "unconnected-(IC3-ASCL-Pad11)") (class "Default")
      (node (ref "IC3") (pin "11") (pinfunction "ASCL_11") (pintype "bidirectional"))
    )
    (net (code "100") (name "unconnected-(IC3-ASDA-Pad4)") (class "Default")
      (node (ref "IC3") (pin "4") (pinfunction "ASDA_4") (pintype "bidirectional"))
    )
    (net (code "101") (name "unconnected-(J1-Pad1)") (class "Default")
      (node (ref "J1") (pin "1") (pinfunction "1_1") (pintype "bidirectional"))
    )
    (net (code "102") (name "unconnected-(J1-Pad6)") (class "Default")
      (node (ref "J1") (pin "6") (pinfunction "6_6") (pintype "bidirectional"))
    )
    (net (code "103") (name "unconnected-(J1-Pad7)") (class "Default")
      (node (ref "J1") (pin "7") (pinfunction "7_7") (pintype "bidirectional"))
    )
    (net (code "104") (name "unconnected-(J3-SBU1-PadA8)") (class "Default")
      (node (ref "J3") (pin "A8") (pinfunction "SBU1_A8") (pintype "bidirectional"))
    )
    (net (code "105") (name "unconnected-(J3-SBU2-PadB8)") (class "Default")
      (node (ref "J3") (pin "B8") (pinfunction "SBU2_B8") (pintype "bidirectional"))
    )
    (net (code "106") (name "unconnected-(U1-DCCH-PadP$AB2)") (class "Default")
      (node (ref "U1") (pin "P$AB2") (pinfunction "DCCH_P$AB2") (pintype "bidirectional"))
    )
  )
)
